# sheet_top.net
KiCad netlist of a schematic drawn in Altium Designer
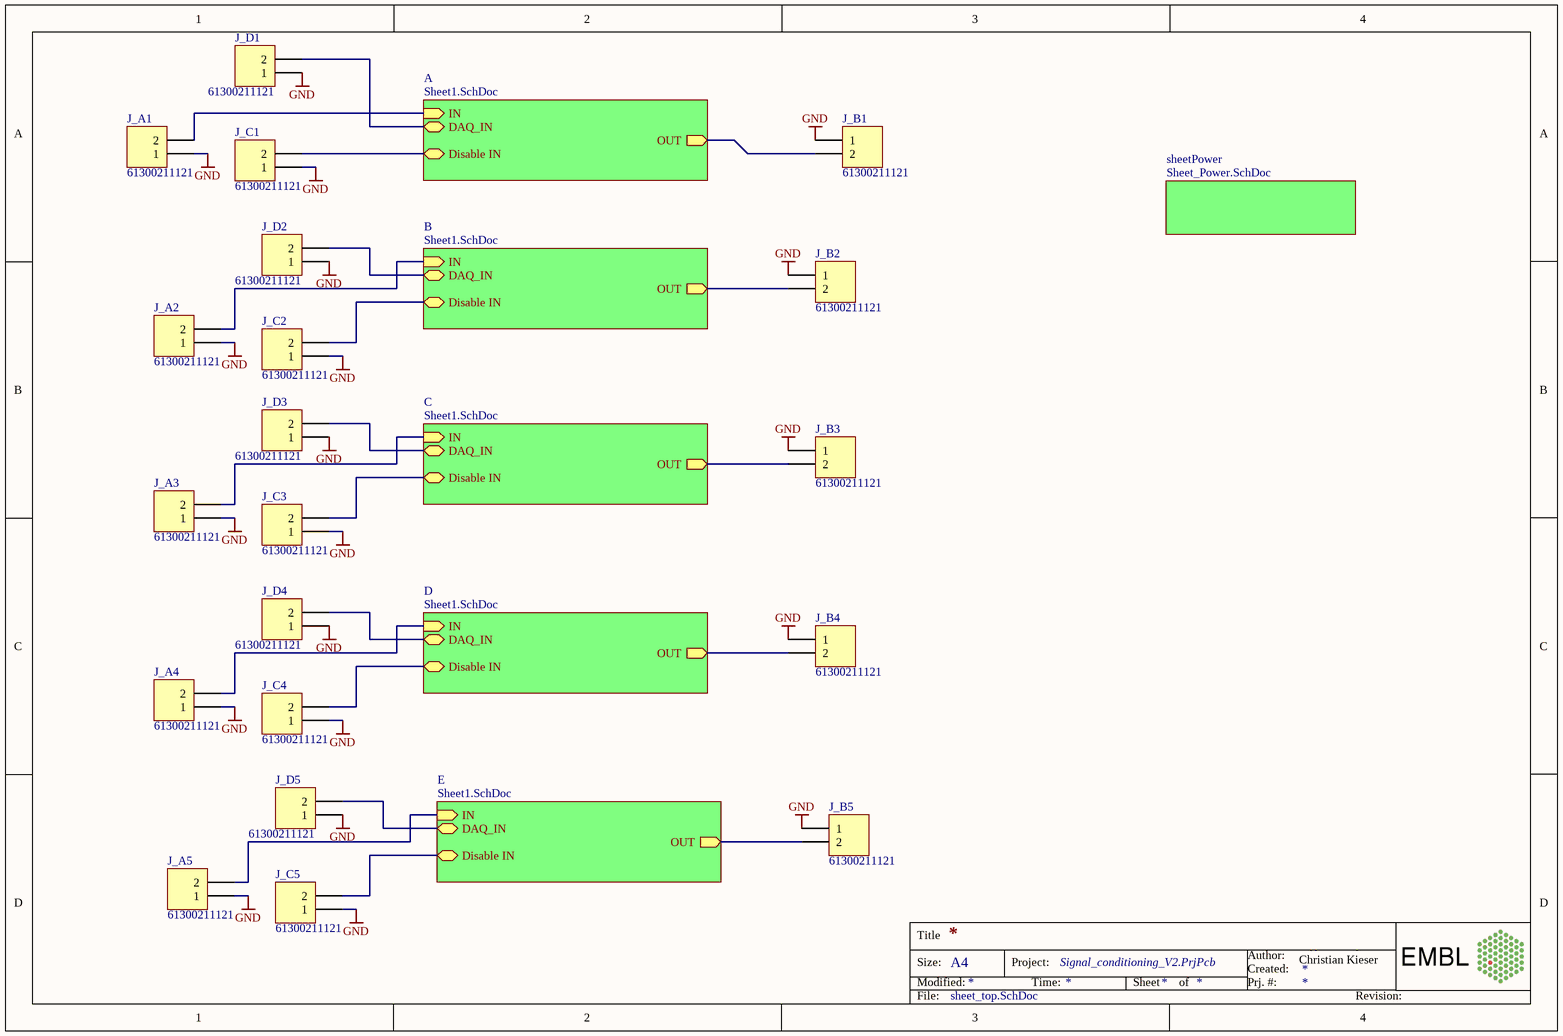
[diagram p0: sheet_top.SchDoc]

(export (version "E")
  (design (tool "Eeschema 10.0.6"))
  (components
    (comp (ref "J_A1")
      (value "61300211121")
      (footprint "61300211121")
      (description "2Pol; gerade; WR-PHD 2.54 mm THT Pin Header")
      (fields (field (name "MANUFACTURER") "Wurth Electronics"))
      (libsource (lib "") (part "CMP-001-0071-1_1"))
    )
    (comp (ref "J_A2")
      (value "61300211121")
      (footprint "61300211121")
      (description "2Pol; gerade; WR-PHD 2.54 mm THT Pin Header")
      (fields (field (name "MANUFACTURER") "Wurth Electronics"))
      (libsource (lib "") (part "CMP-001-0071-1_1"))
    )
    (comp (ref "J_A3")
      (value "61300211121")
      (footprint "61300211121")
      (description "2Pol; gerade; WR-PHD 2.54 mm THT Pin Header")
      (fields (field (name "MANUFACTURER") "Wurth Electronics"))
      (libsource (lib "") (part "CMP-001-0071-1_1"))
    )
    (comp (ref "J_A4")
      (value "61300211121")
      (footprint "61300211121")
      (description "2Pol; gerade; WR-PHD 2.54 mm THT Pin Header")
      (fields (field (name "MANUFACTURER") "Wurth Electronics"))
      (libsource (lib "") (part "CMP-001-0071-1_1"))
    )
    (comp (ref "J_A5")
      (value "61300211121")
      (footprint "61300211121")
      (description "2Pol; gerade; WR-PHD 2.54 mm THT Pin Header")
      (fields (field (name "MANUFACTURER") "Wurth Electronics"))
      (libsource (lib "") (part "CMP-001-0071-1_1"))
    )
    (comp (ref "J_B1")
      (value "61300211121")
      (footprint "61300211121")
      (description "2Pol; gerade; WR-PHD 2.54 mm THT Pin Header")
      (fields (field (name "MANUFACTURER") "Wurth Electronics"))
      (libsource (lib "Altium Vault EMBL 3") (part "61300211121"))
    )
    (comp (ref "J_B2")
      (value "61300211121")
      (footprint "61300211121")
      (description "2Pol; gerade; WR-PHD 2.54 mm THT Pin Header")
      (fields (field (name "MANUFACTURER") "Wurth Electronics"))
      (libsource (lib "Altium Vault EMBL 3") (part "CMP-001-0071-1"))
    )
    (comp (ref "J_B3")
      (value "61300211121")
      (footprint "61300211121")
      (description "2Pol; gerade; WR-PHD 2.54 mm THT Pin Header")
      (fields (field (name "MANUFACTURER") "Wurth Electronics"))
      (libsource (lib "Altium Vault EMBL 3") (part "CMP-001-0071-1"))
    )
    (comp (ref "J_B4")
      (value "61300211121")
      (footprint "61300211121")
      (description "2Pol; gerade; WR-PHD 2.54 mm THT Pin Header")
      (fields (field (name "MANUFACTURER") "Wurth Electronics"))
      (libsource (lib "Altium Vault EMBL 3") (part "CMP-001-0071-1"))
    )
    (comp (ref "J_B5")
      (value "61300211121")
      (footprint "61300211121")
      (description "2Pol; gerade; WR-PHD 2.54 mm THT Pin Header")
      (fields (field (name "MANUFACTURER") "Wurth Electronics"))
      (libsource (lib "Altium Vault EMBL 3") (part "CMP-001-0071-1"))
    )
    (comp (ref "J_C1")
      (value "61300211121")
      (footprint "61300211121")
      (description "2Pol; gerade; WR-PHD 2.54 mm THT Pin Header")
      (fields (field (name "MANUFACTURER") "Wurth Electronics"))
      (libsource (lib "") (part "CMP-001-0071-1_1"))
    )
    (comp (ref "J_C2")
      (value "61300211121")
      (footprint "61300211121")
      (description "2Pol; gerade; WR-PHD 2.54 mm THT Pin Header")
      (fields (field (name "MANUFACTURER") "Wurth Electronics"))
      (libsource (lib "") (part "CMP-001-0071-1_1"))
    )
    (comp (ref "J_C3")
      (value "61300211121")
      (footprint "61300211121")
      (description "2Pol; gerade; WR-PHD 2.54 mm THT Pin Header")
      (fields (field (name "MANUFACTURER") "Wurth Electronics"))
      (libsource (lib "") (part "CMP-001-0071-1_1"))
    )
    (comp (ref "J_C4")
      (value "61300211121")
      (footprint "61300211121")
      (description "2Pol; gerade; WR-PHD 2.54 mm THT Pin Header")
      (fields (field (name "MANUFACTURER") "Wurth Electronics"))
      (libsource (lib "") (part "CMP-001-0071-1_1"))
    )
    (comp (ref "J_C5")
      (value "61300211121")
      (footprint "61300211121")
      (description "2Pol; gerade; WR-PHD 2.54 mm THT Pin Header")
      (fields (field (name "MANUFACTURER") "Wurth Electronics"))
      (libsource (lib "") (part "CMP-001-0071-1_1"))
    )
    (comp (ref "J_D1")
      (value "61300211121")
      (footprint "61300211121")
      (description "2Pol; gerade; WR-PHD 2.54 mm THT Pin Header")
      (fields (field (name "MANUFACTURER") "Wurth Electronics"))
      (libsource (lib "") (part "CMP-001-0071-1_1"))
    )
    (comp (ref "J_D2")
      (value "61300211121")
      (footprint "61300211121")
      (description "2Pol; gerade; WR-PHD 2.54 mm THT Pin Header")
      (fields (field (name "MANUFACTURER") "Wurth Electronics"))
      (libsource (lib "") (part "CMP-001-0071-1_1"))
    )
    (comp (ref "J_D3")
      (value "61300211121")
      (footprint "61300211121")
      (description "2Pol; gerade; WR-PHD 2.54 mm THT Pin Header")
      (fields (field (name "MANUFACTURER") "Wurth Electronics"))
      (libsource (lib "") (part "CMP-001-0071-1_1"))
    )
    (comp (ref "J_D4")
      (value "61300211121")
      (footprint "61300211121")
      (description "2Pol; gerade; WR-PHD 2.54 mm THT Pin Header")
      (fields (field (name "MANUFACTURER") "Wurth Electronics"))
      (libsource (lib "") (part "CMP-001-0071-1_1"))
    )
    (comp (ref "J_D5")
      (value "61300211121")
      (footprint "61300211121")
      (description "2Pol; gerade; WR-PHD 2.54 mm THT Pin Header")
      (fields (field (name "MANUFACTURER") "Wurth Electronics"))
      (libsource (lib "") (part "CMP-001-0071-1_1"))
    )
  )
  (nets
    (net (code "1") (name "/DAQ_IN") (class "Default")
      (node (ref "J_D1") (pin "2") (pinfunction "2_2") (pintype "passive"))
    )
    (net (code "2") (name "/DAQ_IN_1") (class "Default")
      (node (ref "J_D5") (pin "2") (pinfunction "2_2") (pintype "passive"))
    )
    (net (code "3") (name "/DAQ_IN_2") (class "Default")
      (node (ref "J_D4") (pin "2") (pinfunction "2_2") (pintype "passive"))
    )
    (net (code "4") (name "/DAQ_IN_3") (class "Default")
      (node (ref "J_D3") (pin "2") (pinfunction "2_2") (pintype "passive"))
    )
    (net (code "5") (name "/DAQ_IN_4") (class "Default")
      (node (ref "J_D2") (pin "2") (pinfunction "2_2") (pintype "passive"))
    )
    (net (code "6") (name "/Disable IN") (class "Default")
      (node (ref "J_C2") (pin "2") (pinfunction "2_2") (pintype "passive"))
    )
    (net (code "7") (name "/Disable IN_1") (class "Default")
      (node (ref "J_C5") (pin "2") (pinfunction "2_2") (pintype "passive"))
    )
    (net (code "8") (name "/Disable IN_2") (class "Default")
      (node (ref "J_C4") (pin "2") (pinfunction "2_2") (pintype "passive"))
    )
    (net (code "9") (name "/Disable IN_3") (class "Default")
      (node (ref "J_C3") (pin "2") (pinfunction "2_2") (pintype "passive"))
    )
    (net (code "10") (name "/Disable IN_4") (class "Default")
      (node (ref "J_C1") (pin "2") (pinfunction "2_2") (pintype "passive"))
    )
    (net (code "11") (name "/IN") (class "Default")
      (node (ref "J_A1") (pin "2") (pinfunction "2_2") (pintype "passive"))
    )
    (net (code "12") (name "/IN_1") (class "Default")
      (node (ref "J_A5") (pin "2") (pinfunction "2_2") (pintype "passive"))
    )
    (net (code "13") (name "/IN_2") (class "Default")
      (node (ref "J_A4") (pin "2") (pinfunction "2_2") (pintype "passive"))
    )
    (net (code "14") (name "/IN_3") (class "Default")
      (node (ref "J_A3") (pin "2") (pinfunction "2_2") (pintype "passive"))
    )
    (net (code "15") (name "/IN_4") (class "Default")
      (node (ref "J_A2") (pin "2") (pinfunction "2_2") (pintype "passive"))
    )
    (net (code "16") (name "/OUT") (class "Default")
      (node (ref "J_B2") (pin "2") (pinfunction "2_2") (pintype "passive"))
    )
    (net (code "17") (name "/OUT_1") (class "Default")
      (node (ref "J_B4") (pin "2") (pinfunction "2_2") (pintype "passive"))
    )
    (net (code "18") (name "/OUT_2") (class "Default")
      (node (ref "J_B5") (pin "2") (pinfunction "2_2") (pintype "passive"))
    )
    (net (code "19") (name "/OUT_3") (class "Default")
      (node (ref "J_B3") (pin "2") (pinfunction "2_2") (pintype "passive"))
    )
    (net (code "20") (name "/OUT_4") (class "Default")
      (node (ref "J_B1") (pin "2") (pinfunction "2_2") (pintype "passive"))
    )
    (net (code "21") (name "GND") (class "Default")
      (node (ref "J_A1") (pin "1") (pinfunction "1_1") (pintype "passive"))
      (node (ref "J_A2") (pin "1") (pinfunction "1_1") (pintype "passive"))
      (node (ref "J_A3") (pin "1") (pinfunction "1_1") (pintype "passive"))
      (node (ref "J_A4") (pin "1") (pinfunction "1_1") (pintype "passive"))
      (node (ref "J_A5") (pin "1") (pinfunction "1_1") (pintype "passive"))
      (node (ref "J_B1") (pin "1") (pinfunction "1_1") (pintype "passive"))
      (node (ref "J_B2") (pin "1") (pinfunction "1_1") (pintype "passive"))
      (node (ref "J_B3") (pin "1") (pinfunction "1_1") (pintype "passive"))
      (node (ref "J_B4") (pin "1") (pinfunction "1_1") (pintype "passive"))
      (node (ref "J_B5") (pin "1") (pinfunction "1_1") (pintype "passive"))
      (node (ref "J_C1") (pin "1") (pinfunction "1_1") (pintype "passive"))
      (node (ref "J_C2") (pin "1") (pinfunction "1_1") (pintype "passive"))
      (node (ref "J_C3") (pin "1") (pinfunction "1_1") (pintype "passive"))
      (node (ref "J_C4") (pin "1") (pinfunction "1_1") (pintype "passive"))
      (node (ref "J_C5") (pin "1") (pinfunction "1_1") (pintype "passive"))
      (node (ref "J_D1") (pin "1") (pinfunction "1_1") (pintype "passive"))
      (node (ref "J_D2") (pin "1") (pinfunction "1_1") (pintype "passive"))
      (node (ref "J_D3") (pin "1") (pinfunction "1_1") (pintype "passive"))
      (node (ref "J_D4") (pin "1") (pinfunction "1_1") (pintype "passive"))
      (node (ref "J_D5") (pin "1") (pinfunction "1_1") (pintype "passive"))
    )
  )
)
